# H09R00.net
KiCad netlist of a schematic drawn in EAGLE
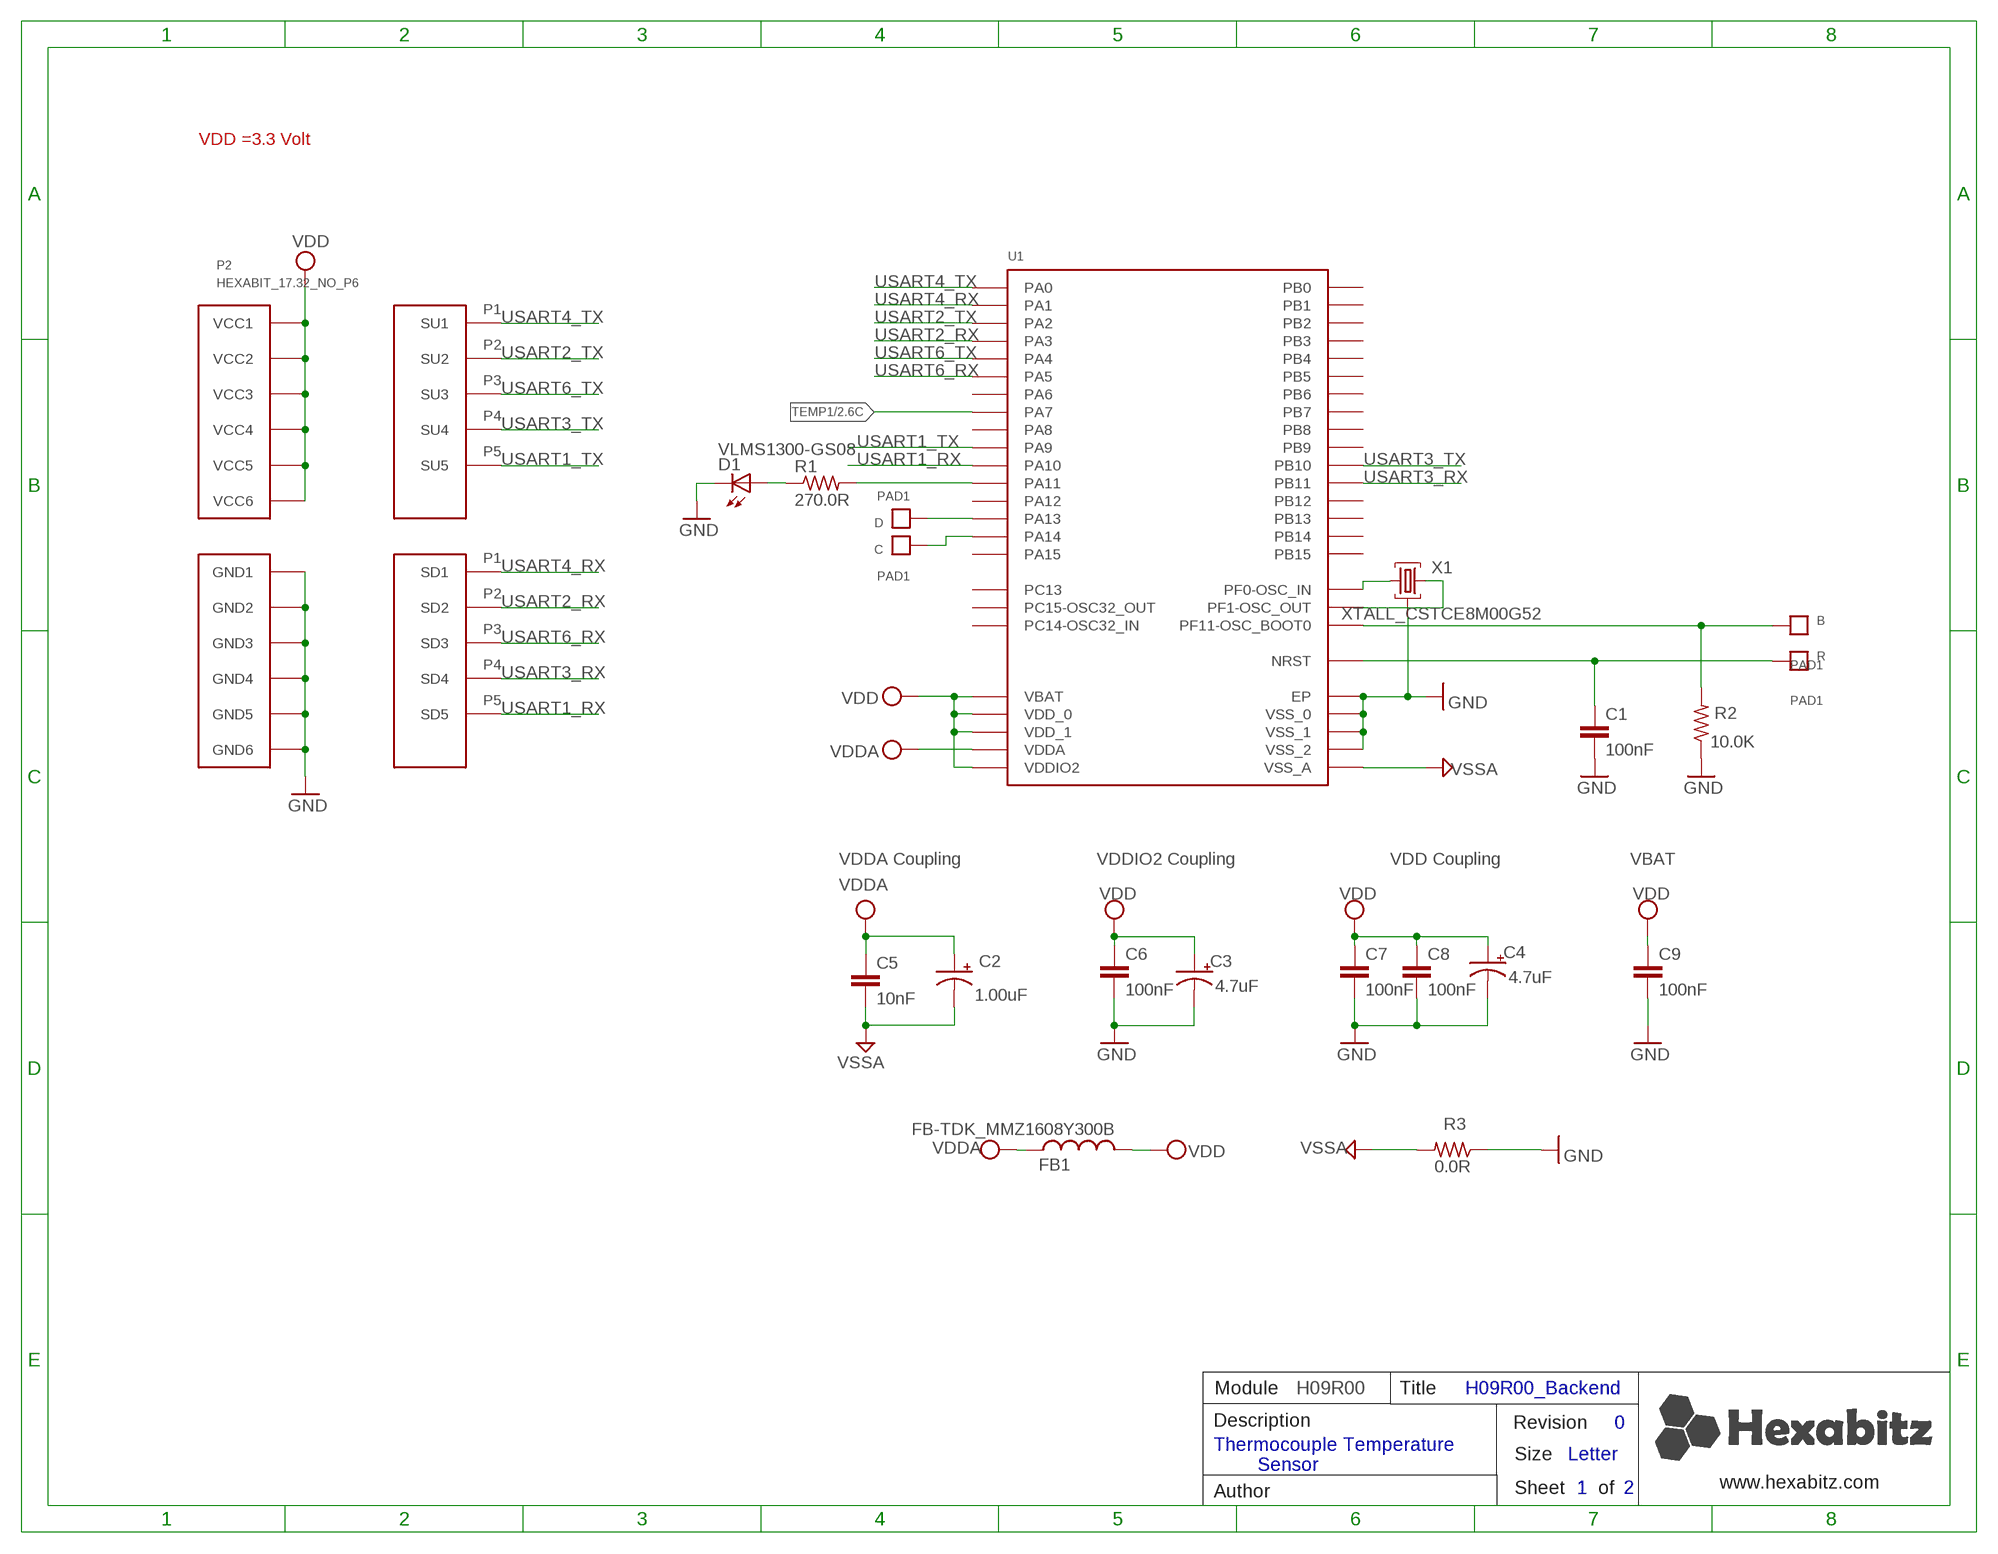
[diagram p0: schematic, sheet 1]
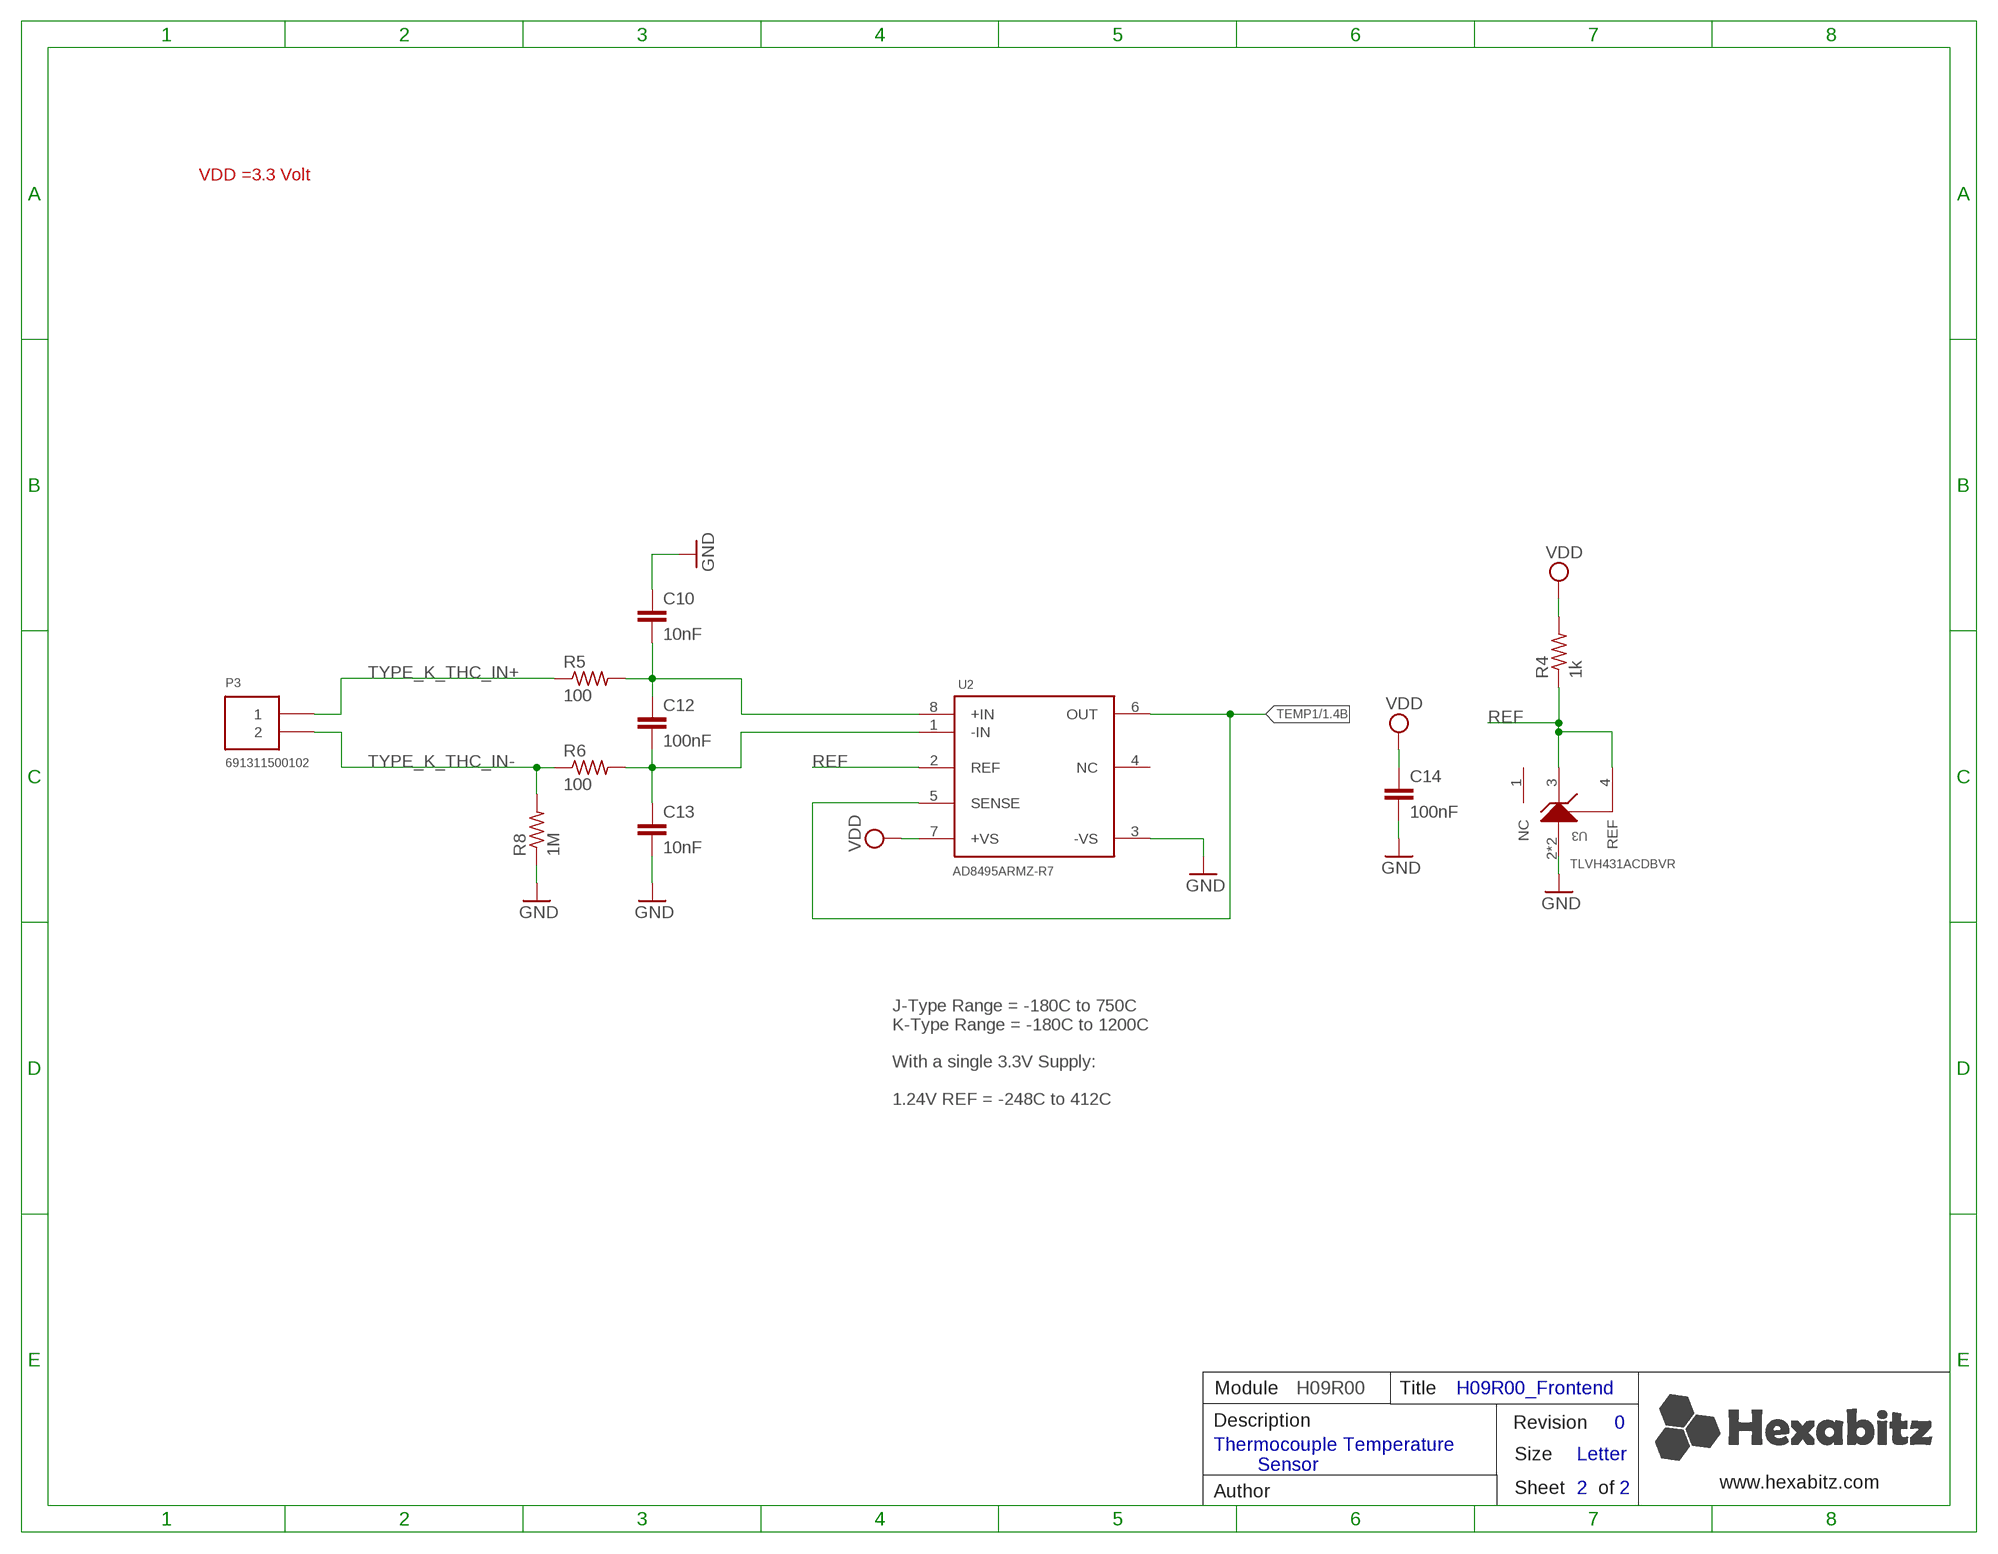
[diagram p1: schematic, sheet 2]

(export (version "E")
  (design (tool "Eeschema 10.0.6"))
  (components
    (comp (ref "B")
      (value "PAD1")
      (footprint "eagle-import:PAD1")
      (libsource (lib "eagle-import") (part "PAD1"))
    )
    (comp (ref "C")
      (value "PAD1")
      (footprint "eagle-import:PAD1")
      (libsource (lib "eagle-import") (part "PAD1"))
    )
    (comp (ref "C1")
      (value "100nF")
      (footprint "eagle-import:C-0603")
      (fields
        (field (name "CAPACITANCE") "100nF")
        (field (name "MFN") "KEMET")
        (field (name "MPN") "C0603C104K8RACTU")
        (field (name "OCTOPART_URL") "https://octopart.com/c0603c104k8ractu-kemet-145075?r=sp&s=9bS9ASSwSEqMCE9KBEQZ0g")
        (field (name "TOLERANCE") "10%")
        (field (name "VOLTAGE_RATING") "10V")
      )
      (libsource (lib "eagle-import") (part "C-0603"))
    )
    (comp (ref "C2")
      (value "1.00uF")
      (footprint "eagle-import:C-0805-POL")
      (fields
        (field (name "CAPACITANCE") "1.00uF")
        (field (name "MFN") "Yageo")
        (field (name "MPN") "CC0805KKX7R7BB105")
        (field (name "OCTOPART_URL") "https://octopart.com/cc0805kkx7r7bb105-yageo-8376555?r=sp&s=YKl1wwtkROau_X5nniH2ig")
        (field (name "TOLERANCE") "10%")
        (field (name "VOLTAGE_RATING") "16V")
      )
      (libsource (lib "eagle-import") (part "C-0805-POL"))
    )
    (comp (ref "C3")
      (value "4.7uF")
      (footprint "eagle-import:C-0805-POL")
      (fields
        (field (name "CAPACITANCE") "4.7uF")
        (field (name "MFN") "Murata")
        (field (name "MPN") "GRM21BC81E475KA12L")
        (field (name "OCTOPART_URL") "https://octopart.com/grm21bc81e475ka12l-murata-10331911?r=sp&s=RY3qZSD8T6mG6TC9CHI5qQ")
        (field (name "TOLERANCE") "10%")
        (field (name "VOLTAGE_RATING") "25V")
      )
      (libsource (lib "eagle-import") (part "C-0805-POL"))
    )
    (comp (ref "C4")
      (value "4.7uF")
      (footprint "eagle-import:C-0805-POL")
      (fields
        (field (name "CAPACITANCE") "4.7uF")
        (field (name "MFN") "Murata")
        (field (name "MPN") "GRM21BC81E475KA12L")
        (field (name "OCTOPART_URL") "https://octopart.com/grm21bc81e475ka12l-murata-10331911?r=sp&s=RY3qZSD8T6mG6TC9CHI5qQ")
        (field (name "TOLERANCE") "10%")
        (field (name "VOLTAGE_RATING") "25V")
      )
      (libsource (lib "eagle-import") (part "C-0805-POL"))
    )
    (comp (ref "C5")
      (value "10nF")
      (footprint "eagle-import:C-0603")
      (fields
        (field (name "CAPACITANCE") "10nF")
        (field (name "MFN") "KEMET")
        (field (name "MPN") "C0603C103K5RACTU")
        (field (name "OCTOPART_URL") "https://octopart.com/c0603c103k5ractu-kemet-133094?r=sp&s=R_iPBxLnSmGqhkU2rIMFpg")
        (field (name "TOLERANCE") "10%")
        (field (name "VOLTAGE_RATING") "50V")
      )
      (libsource (lib "eagle-import") (part "C-0603"))
    )
    (comp (ref "C6")
      (value "100nF")
      (footprint "eagle-import:C-0603")
      (fields
        (field (name "CAPACITANCE") "100nF")
        (field (name "MFN") "KEMET")
        (field (name "MPN") "C0603C104K8RACTU")
        (field (name "OCTOPART_URL") "https://octopart.com/c0603c104k8ractu-kemet-145075?r=sp&s=9bS9ASSwSEqMCE9KBEQZ0g")
        (field (name "TOLERANCE") "10%")
        (field (name "VOLTAGE_RATING") "10V")
      )
      (libsource (lib "eagle-import") (part "C-0603"))
    )
    (comp (ref "C7")
      (value "100nF")
      (footprint "eagle-import:C-0603")
      (fields
        (field (name "CAPACITANCE") "100nF")
        (field (name "MFN") "KEMET")
        (field (name "MPN") "C0603C104K8RACTU")
        (field (name "OCTOPART_URL") "https://octopart.com/c0603c104k8ractu-kemet-145075?r=sp&s=9bS9ASSwSEqMCE9KBEQZ0g")
        (field (name "TOLERANCE") "10%")
        (field (name "VOLTAGE_RATING") "10")
      )
      (libsource (lib "eagle-import") (part "C-0603"))
    )
    (comp (ref "C8")
      (value "100nF")
      (footprint "eagle-import:C-0603")
      (fields
        (field (name "CAPACITANCE") "100nF")
        (field (name "MFN") "KEMET")
        (field (name "MPN") "C0603C104K8RACTU")
        (field (name "OCTOPART_URL") "https://octopart.com/c0603c104k8ractu-kemet-145075?r=sp&s=9bS9ASSwSEqMCE9KBEQZ0g")
        (field (name "TOLERANCE") "10%")
        (field (name "VOLTAGE_RATING") "10V")
      )
      (libsource (lib "eagle-import") (part "C-0603"))
    )
    (comp (ref "C9")
      (value "100nF")
      (footprint "eagle-import:C-0603")
      (fields
        (field (name "CAPACITANCE") "100nF")
        (field (name "MFN") "KEMET")
        (field (name "MPN") "C0603C104K8RACTU")
        (field (name "OCTOPART_URL") "https://octopart.com/c0603c104k8ractu-kemet-145075?r=sp&s=9bS9ASSwSEqMCE9KBEQZ0g")
        (field (name "TOLERANCE") "10V")
        (field (name "VOLTAGE_RATING") "10%")
      )
      (libsource (lib "eagle-import") (part "C-0603"))
    )
    (comp (ref "D")
      (value "PAD1")
      (footprint "eagle-import:PAD1")
      (libsource (lib "eagle-import") (part "PAD1"))
    )
    (comp (ref "D1")
      (value "VLMS1300-GS08")
      (footprint "eagle-import:VLMS1300-GS08")
      (fields
        (field (name "MFN") "Vishay")
        (field (name "MPN") "VLMS1300-GS08")
        (field (name "OCTOPART_URL") "https://octopart.com/vlms1300-gs08-vishay-21709201?r=sp&s=_gcP4_q8T1SC6PJQPTQ9yA")
      )
      (libsource (lib "eagle-import") (part "VLMS1300-GS08"))
    )
    (comp (ref "FB1")
      (value "FB-TDK_MMZ1608Y300B")
      (footprint "eagle-import:FB-TDK_MMZ1608Y300B")
      (fields
        (field (name "MFN") "TDK ")
        (field (name "MPN") "MMZ1608Y300B")
        (field (name "OCTOPART_URL") "https://octopart.com/mmz1608y300b-tdk-368280?r=sp&s=cd9_2ZEqQ9q9UNBuQgHAiA")
      )
      (libsource (lib "eagle-import") (part "FB-TDK_MMZ1608Y300B"))
    )
    (comp (ref "P2")
      (value "HEXABIT_17.32_NO_P6")
      (footprint "eagle-import:HEXABIT_17.32_NO_P6")
      (libsource (lib "eagle-import") (part "HEXABIT_17.32_NO_P6"))
    )
    (comp (ref "R")
      (value "PAD1")
      (footprint "eagle-import:PAD1")
      (libsource (lib "eagle-import") (part "PAD1"))
    )
    (comp (ref "R1")
      (value "270.0R")
      (footprint "eagle-import:R-0603")
      (fields
        (field (name "MFN") "Yageo")
        (field (name "MPN") "RC0603FR-07270RL")
        (field (name "OCTOPART_URL") "https://octopart.com/search?q=RC0603FR-07270RL&start=0")
        (field (name "RESISTANCE") "270.0 Ohm")
        (field (name "TOLERANCE") "1%")
      )
      (libsource (lib "eagle-import") (part "R-0603"))
    )
    (comp (ref "R2")
      (value "10.0K")
      (footprint "eagle-import:R-0603")
      (fields
        (field (name "MFN") "Yageo")
        (field (name "MPN") "RC0603JR-0710KL")
        (field (name "OCTOPART_URL") "https://octopart.com/search?q=RC0603JR-0710KL&start=0")
        (field (name "RESISTANCE") "10.0K Ohm")
        (field (name "TOLERANCE") "5%")
      )
      (libsource (lib "eagle-import") (part "R-0603"))
    )
    (comp (ref "R3")
      (value "0.0R")
      (footprint "eagle-import:R-0603")
      (fields
        (field (name "MFN") "Yageo")
        (field (name "MPN") "RC0603JR-070RL")
        (field (name "OCTOPART_URL") "https://octopart.com/rc0603jr-070rl-yageo-1241539?r=sp&s=X2NteqRjRNWrnx42Y0aliA")
        (field (name "RESISTANCE") "0.0 Ohm")
      )
      (libsource (lib "eagle-import") (part "R-0603"))
    )
    (comp (ref "U1")
      (value "STM32F091CBU6")
      (footprint "eagle-import:STM32F091CBU6")
      (libsource (lib "eagle-import") (part "STM32F091CBU6"))
    )
    (comp (ref "X1")
      (value "XTALL_CSTCE8M00G52")
      (footprint "eagle-import:XTALL_CSTCE8M00G52")
      (fields (field (name "MPN") "CSTCE8M00G52Z-R0"))
      (libsource (lib "eagle-import") (part "XTALL_CSTCE8M00G52"))
    )
    (comp (ref "C10")
      (value "10nF")
      (footprint "eagle-import:C-0603")
      (fields
        (field (name "CAPACITANCE") "10nF")
        (field (name "MFN") "KEMET")
        (field (name "MPN") "C0603C103K5RACTU")
        (field (name "OCTOPART_URL") "https://octopart.com/c0603c103k5ractu-kemet-133094?r=sp&s=R_iPBxLnSmGqhkU2rIMFpg")
        (field (name "TOLERANCE") "10%")
        (field (name "VOLTAGE_RATING") "50V")
      )
      (libsource (lib "eagle-import") (part "C-0603"))
    )
    (comp (ref "C12")
      (value "100nF")
      (footprint "eagle-import:C-0603")
      (fields
        (field (name "CAPACITANCE") "100nF")
        (field (name "MFN") "KEMET")
        (field (name "MPN") "C0603C104K8RACTU")
        (field (name "OCTOPART_URL") "https://octopart.com/c0603c104k8ractu-kemet-145075?r=sp&s=9bS9ASSwSEqMCE9KBEQZ0g")
        (field (name "TOLERANCE") "10%")
        (field (name "VOLTAGE_RATING") "10V")
      )
      (libsource (lib "eagle-import") (part "C-0603"))
    )
    (comp (ref "C13")
      (value "10nF")
      (footprint "eagle-import:C-0603")
      (fields
        (field (name "CAPACITANCE") "10nF")
        (field (name "MFN") "KEMET")
        (field (name "MPN") "C0603C103K5RACTU")
        (field (name "OCTOPART_URL") "https://octopart.com/c0603c103k5ractu-kemet-133094?r=sp&s=R_iPBxLnSmGqhkU2rIMFpg")
        (field (name "TOLERANCE") "10%")
        (field (name "VOLTAGE_RATING") "50V")
      )
      (libsource (lib "eagle-import") (part "C-0603"))
    )
    (comp (ref "C14")
      (value "100nF")
      (footprint "eagle-import:C-0603")
      (fields
        (field (name "CAPACITANCE") "100nF")
        (field (name "MFN") "KEMET")
        (field (name "MPN") "C0603C104K8RACTU")
        (field (name "OCTOPART_URL") "https://octopart.com/c0603c104k8ractu-kemet-145075?r=sp&s=9bS9ASSwSEqMCE9KBEQZ0g")
        (field (name "TOLERANCE") "10%")
        (field (name "VOLTAGE_RATING") "10V")
      )
      (libsource (lib "eagle-import") (part "C-0603"))
    )
    (comp (ref "P3")
      (value "691311500102")
      (footprint "eagle-import:691311500102")
      (fields (field (name "MPN") "Wurth Electronics Inc."))
      (libsource (lib "eagle-import") (part "691311500102"))
    )
    (comp (ref "R4")
      (value "1k")
      (footprint "eagle-import:R-0402")
      (fields
        (field (name "MFN") "Yageo")
        (field (name "MPN") "RC0402FR-071KL")
        (field (name "OCTOPART_URL") "https://octopart.com/search?q=RC0402FR-071KL&start=0")
        (field (name "RESISTANCE") "1k")
        (field (name "TOLERANCE") "1%")
      )
      (libsource (lib "eagle-import") (part "R-0402"))
    )
    (comp (ref "R5")
      (value "100")
      (footprint "eagle-import:R-0402")
      (fields
        (field (name "MFN") "Yageo")
        (field (name "MPN") "RC0402FR-07100RL")
        (field (name "OCTOPART_URL") "https://octopart.com/search?q=RC0402FR-07100RL&start=0")
        (field (name "RESISTANCE") "100")
        (field (name "TOLERANCE") "1%")
      )
      (libsource (lib "eagle-import") (part "R-0402"))
    )
    (comp (ref "R6")
      (value "100")
      (footprint "eagle-import:R-0402")
      (fields
        (field (name "MFN") "Yageo")
        (field (name "MPN") "RC0402FR-07100RL")
        (field (name "OCTOPART_URL") "https://octopart.com/search?q=RC0402FR-07100RL&start=0")
        (field (name "RESISTANCE") "100")
        (field (name "TOLERANCE") "1%")
      )
      (libsource (lib "eagle-import") (part "R-0402"))
    )
    (comp (ref "R8")
      (value "1M")
      (footprint "eagle-import:R-0402")
      (fields
        (field (name "MFN") "Yageo")
        (field (name "MPN") "RC0402FR-071ML")
        (field (name "OCTOPART_URL") "https://octopart.com/search?q=RC0402FR-071ML&start=0")
        (field (name "RESISTANCE") "1M")
        (field (name "TOLERANCE") "1%")
      )
      (libsource (lib "eagle-import") (part "R-0402"))
    )
    (comp (ref "U2")
      (value "AD8495ARMZ-R7")
      (footprint "eagle-import:AD8495ARMZ")
      (fields (field (name "MFG") "Analog Devices"))
      (libsource (lib "eagle-import") (part "AD8495ARMZ"))
    )
    (comp (ref "U3")
      (value "TLVH431ACDBVR")
      (footprint "eagle-import:TLVH431ACDBVR")
      (libsource (lib "eagle-import") (part "TLVH431ACDBVR"))
    )
  )
  (nets
    (net (code "1") (name "GND") (class "Default")
      (node (ref "C1") (pin "2") (pinfunction "2_2") (pintype "passive"))
      (node (ref "C10") (pin "1") (pinfunction "1_1") (pintype "passive"))
      (node (ref "C13") (pin "2") (pinfunction "2_2") (pintype "passive"))
      (node (ref "C14") (pin "2") (pinfunction "2_2") (pintype "passive"))
      (node (ref "C3") (pin "2") (pinfunction "-_2") (pintype "passive"))
      (node (ref "C4") (pin "2") (pinfunction "-_2") (pintype "passive"))
      (node (ref "C6") (pin "2") (pinfunction "2_2") (pintype "passive"))
      (node (ref "C7") (pin "2") (pinfunction "2_2") (pintype "passive"))
      (node (ref "C8") (pin "2") (pinfunction "2_2") (pintype "passive"))
      (node (ref "C9") (pin "2") (pinfunction "2_2") (pintype "passive"))
      (node (ref "D1") (pin "C") (pinfunction "C_C") (pintype "passive"))
      (node (ref "P2") (pin "10") (pinfunction "GND4_10") (pintype "power_in"))
      (node (ref "P2") (pin "11") (pinfunction "GND5_11") (pintype "power_in"))
      (node (ref "P2") (pin "12") (pinfunction "GND6_12") (pintype "power_in"))
      (node (ref "P2") (pin "7") (pinfunction "GND1_7") (pintype "power_in"))
      (node (ref "P2") (pin "8") (pinfunction "GND2_8") (pintype "power_in"))
      (node (ref "P2") (pin "9") (pinfunction "GND3_9") (pintype "power_in"))
      (node (ref "R2") (pin "1") (pinfunction "1_1") (pintype "passive"))
      (node (ref "R3") (pin "1") (pinfunction "1_1") (pintype "passive"))
      (node (ref "R8") (pin "1") (pinfunction "1_1") (pintype "passive"))
      (node (ref "U1") (pin "EP") (pinfunction "EP_EP") (pintype "power_in"))
      (node (ref "U1") (pin "P$23") (pinfunction "VSS_0_P$23") (pintype "power_in"))
      (node (ref "U1") (pin "P$35") (pinfunction "VSS_1_P$35") (pintype "power_in"))
      (node (ref "U1") (pin "P$47") (pinfunction "VSS_2_P$47") (pintype "power_in"))
      (node (ref "U2") (pin "3") (pinfunction "-VS_3") (pintype "power_in"))
      (node (ref "U3") (pin "2") (pinfunction "ANODE_2") (pintype "input"))
      (node (ref "U3") (pin "5") (pinfunction "ANODE_5") (pintype "input"))
      (node (ref "X1") (pin "P$2") (pinfunction "2_P$2") (pintype "passive"))
    )
    (net (code "2") (name "Net-(D1-PadA)") (class "Default")
      (node (ref "D1") (pin "A") (pinfunction "A_A") (pintype "passive"))
      (node (ref "R1") (pin "1") (pinfunction "1_1") (pintype "passive"))
    )
    (net (code "3") (name "Net-(U1-NRST)") (class "Default")
      (node (ref "C1") (pin "1") (pinfunction "1_1") (pintype "passive"))
      (node (ref "R") (pin "P$1") (pinfunction "P$1_P$1") (pintype "passive"))
      (node (ref "R") (pin "P$2") (pinfunction "P$1_P$2") (pintype "passive"))
      (node (ref "U1") (pin "P$7") (pinfunction "NRST_P$7") (pintype "passive"))
    )
    (net (code "4") (name "Net-(U1-PA11)") (class "Default")
      (node (ref "R1") (pin "2") (pinfunction "2_2") (pintype "passive"))
      (node (ref "U1") (pin "P$32") (pinfunction "PA11_P$32") (pintype "bidirectional"))
    )
    (net (code "5") (name "Net-(U1-PA13)") (class "Default")
      (node (ref "D") (pin "P$1") (pinfunction "P$1_P$1") (pintype "passive"))
      (node (ref "D") (pin "P$2") (pinfunction "P$1_P$2") (pintype "passive"))
      (node (ref "U1") (pin "P$34") (pinfunction "PA13_P$34") (pintype "bidirectional"))
    )
    (net (code "6") (name "Net-(U1-PA14)") (class "Default")
      (node (ref "C") (pin "P$1") (pinfunction "P$1_P$1") (pintype "passive"))
      (node (ref "C") (pin "P$2") (pinfunction "P$1_P$2") (pintype "passive"))
      (node (ref "U1") (pin "P$37") (pinfunction "PA14_P$37") (pintype "bidirectional"))
    )
    (net (code "7") (name "Net-(U1-PF0-OSC_IN)") (class "Default")
      (node (ref "U1") (pin "P$5") (pinfunction "PF0-OSC_IN_P$5") (pintype "bidirectional"))
      (node (ref "X1") (pin "P$1") (pinfunction "1_P$1") (pintype "passive"))
    )
    (net (code "8") (name "Net-(U1-PF1-OSC_OUT)") (class "Default")
      (node (ref "U1") (pin "P$6") (pinfunction "PF1-OSC_OUT_P$6") (pintype "bidirectional"))
      (node (ref "X1") (pin "P$3") (pinfunction "3_P$3") (pintype "passive"))
    )
    (net (code "9") (name "Net-(U1-PF11-OSC_BOOT0)") (class "Default")
      (node (ref "B") (pin "P$1") (pinfunction "P$1_P$1") (pintype "passive"))
      (node (ref "B") (pin "P$2") (pinfunction "P$1_P$2") (pintype "passive"))
      (node (ref "R2") (pin "2") (pinfunction "2_2") (pintype "passive"))
      (node (ref "U1") (pin "P$44") (pinfunction "PF11-OSC_BOOT0_P$44") (pintype "bidirectional"))
    )
    (net (code "10") (name "Net-(U2-+IN)") (class "Default")
      (node (ref "C10") (pin "2") (pinfunction "2_2") (pintype "passive"))
      (node (ref "C12") (pin "1") (pinfunction "1_1") (pintype "passive"))
      (node (ref "R5") (pin "2") (pinfunction "2_2") (pintype "passive"))
      (node (ref "U2") (pin "8") (pinfunction "+IN_8") (pintype "bidirectional"))
    )
    (net (code "11") (name "Net-(U2--IN)") (class "Default")
      (node (ref "C12") (pin "2") (pinfunction "2_2") (pintype "passive"))
      (node (ref "C13") (pin "1") (pinfunction "1_1") (pintype "passive"))
      (node (ref "R6") (pin "2") (pinfunction "2_2") (pintype "passive"))
      (node (ref "U2") (pin "1") (pinfunction "-IN_1") (pintype "bidirectional"))
    )
    (net (code "12") (name "REF") (class "Default")
      (node (ref "R4") (pin "1") (pinfunction "1_1") (pintype "passive"))
      (node (ref "U2") (pin "2") (pinfunction "REF_2") (pintype "bidirectional"))
      (node (ref "U3") (pin "3") (pinfunction "CATHODE_3") (pintype "output"))
      (node (ref "U3") (pin "4") (pinfunction "REF_4") (pintype "input"))
    )
    (net (code "13") (name "TEMP1") (class "Default")
      (node (ref "U1") (pin "P$17") (pinfunction "PA7_P$17") (pintype "bidirectional"))
      (node (ref "U2") (pin "5") (pinfunction "SENSE_5") (pintype "bidirectional"))
      (node (ref "U2") (pin "6") (pinfunction "OUT_6") (pintype "output"))
    )
    (net (code "14") (name "TYPE_K_THC_IN+") (class "Default")
      (node (ref "P3") (pin "1") (pinfunction "1_1") (pintype "power_in"))
      (node (ref "R5") (pin "1") (pinfunction "1_1") (pintype "passive"))
    )
    (net (code "15") (name "TYPE_K_THC_IN-") (class "Default")
      (node (ref "P3") (pin "2") (pinfunction "2_2") (pintype "power_in"))
      (node (ref "R6") (pin "1") (pinfunction "1_1") (pintype "passive"))
      (node (ref "R8") (pin "2") (pinfunction "2_2") (pintype "passive"))
    )
    (net (code "16") (name "USART1_RX") (class "Default")
      (node (ref "P2") (pin "23") (pinfunction "SD5_23") (pintype "bidirectional"))
      (node (ref "U1") (pin "P$31") (pinfunction "PA10_P$31") (pintype "bidirectional"))
    )
    (net (code "17") (name "USART1_TX") (class "Default")
      (node (ref "P2") (pin "17") (pinfunction "SU5_17") (pintype "bidirectional"))
      (node (ref "U1") (pin "P$30") (pinfunction "PA9_P$30") (pintype "bidirectional"))
    )
    (net (code "18") (name "USART2_RX") (class "Default")
      (node (ref "P2") (pin "20") (pinfunction "SD2_20") (pintype "bidirectional"))
      (node (ref "U1") (pin "P$13") (pinfunction "PA3_P$13") (pintype "bidirectional"))
    )
    (net (code "19") (name "USART2_TX") (class "Default")
      (node (ref "P2") (pin "14") (pinfunction "SU2_14") (pintype "bidirectional"))
      (node (ref "U1") (pin "P$12") (pinfunction "PA2_P$12") (pintype "bidirectional"))
    )
    (net (code "20") (name "USART3_RX") (class "Default")
      (node (ref "P2") (pin "22") (pinfunction "SD4_22") (pintype "bidirectional"))
      (node (ref "U1") (pin "P$22") (pinfunction "PB11_P$22") (pintype "bidirectional"))
    )
    (net (code "21") (name "USART3_TX") (class "Default")
      (node (ref "P2") (pin "16") (pinfunction "SU4_16") (pintype "bidirectional"))
      (node (ref "U1") (pin "P$21") (pinfunction "PB10_P$21") (pintype "bidirectional"))
    )
    (net (code "22") (name "USART4_RX") (class "Default")
      (node (ref "P2") (pin "19") (pinfunction "SD1_19") (pintype "bidirectional"))
      (node (ref "U1") (pin "P$11") (pinfunction "PA1_P$11") (pintype "bidirectional"))
    )
    (net (code "23") (name "USART4_TX") (class "Default")
      (node (ref "P2") (pin "13") (pinfunction "SU1_13") (pintype "bidirectional"))
      (node (ref "U1") (pin "P$10") (pinfunction "PA0_P$10") (pintype "bidirectional"))
    )
    (net (code "24") (name "USART6_RX") (class "Default")
      (node (ref "P2") (pin "21") (pinfunction "SD3_21") (pintype "bidirectional"))
      (node (ref "U1") (pin "P$15") (pinfunction "PA5_P$15") (pintype "bidirectional"))
    )
    (net (code "25") (name "USART6_TX") (class "Default")
      (node (ref "P2") (pin "15") (pinfunction "SU3_15") (pintype "bidirectional"))
      (node (ref "U1") (pin "P$14") (pinfunction "PA4_P$14") (pintype "bidirectional"))
    )
    (net (code "26") (name "VDD") (class "Default")
      (node (ref "C14") (pin "1") (pinfunction "1_1") (pintype "passive"))
      (node (ref "C3") (pin "1") (pinfunction "+_1") (pintype "passive"))
      (node (ref "C4") (pin "1") (pinfunction "+_1") (pintype "passive"))
      (node (ref "C6") (pin "1") (pinfunction "1_1") (pintype "passive"))
      (node (ref "C7") (pin "1") (pinfunction "1_1") (pintype "passive"))
      (node (ref "C8") (pin "1") (pinfunction "1_1") (pintype "passive"))
      (node (ref "C9") (pin "1") (pinfunction "1_1") (pintype "passive"))
      (node (ref "FB1") (pin "2") (pinfunction "2_2") (pintype "passive"))
      (node (ref "P2") (pin "1") (pinfunction "VCC1_1") (pintype "power_in"))
      (node (ref "P2") (pin "2") (pinfunction "VCC2_2") (pintype "power_in"))
      (node (ref "P2") (pin "3") (pinfunction "VCC3_3") (pintype "power_in"))
      (node (ref "P2") (pin "4") (pinfunction "VCC4_4") (pintype "power_in"))
      (node (ref "P2") (pin "5") (pinfunction "VCC5_5") (pintype "power_in"))
      (node (ref "P2") (pin "6") (pinfunction "VCC6_6") (pintype "power_in"))
      (node (ref "R4") (pin "2") (pinfunction "2_2") (pintype "passive"))
      (node (ref "U1") (pin "P$1") (pinfunction "VBAT_P$1") (pintype "power_in"))
      (node (ref "U1") (pin "P$24") (pinfunction "VDD_0_P$24") (pintype "power_in"))
      (node (ref "U1") (pin "P$36") (pinfunction "VDDIO2_P$36") (pintype "power_in"))
      (node (ref "U1") (pin "P$48") (pinfunction "VDD_1_P$48") (pintype "power_in"))
      (node (ref "U2") (pin "7") (pinfunction "+VS_7") (pintype "power_in"))
    )
    (net (code "27") (name "VDDA") (class "Default")
      (node (ref "C2") (pin "1") (pinfunction "+_1") (pintype "passive"))
      (node (ref "C5") (pin "1") (pinfunction "1_1") (pintype "passive"))
      (node (ref "FB1") (pin "1") (pinfunction "1_1") (pintype "passive"))
      (node (ref "U1") (pin "P$9") (pinfunction "VDDA_P$9") (pintype "power_in"))
    )
    (net (code "28") (name "VSSA") (class "Default")
      (node (ref "C2") (pin "2") (pinfunction "-_2") (pintype "passive"))
      (node (ref "C5") (pin "2") (pinfunction "2_2") (pintype "passive"))
      (node (ref "R3") (pin "2") (pinfunction "2_2") (pintype "passive"))
      (node (ref "U1") (pin "P$8") (pinfunction "VSS_A_P$8") (pintype "power_in"))
    )
    (net (code "29") (name "unconnected-(U1-PA6-PadP$16)") (class "Default")
      (node (ref "U1") (pin "P$16") (pinfunction "PA6_P$16") (pintype "bidirectional"))
    )
    (net (code "30") (name "unconnected-(U1-PA8-PadP$29)") (class "Default")
      (node (ref "U1") (pin "P$29") (pinfunction "PA8_P$29") (pintype "bidirectional"))
    )
    (net (code "31") (name "unconnected-(U1-PA12-PadP$33)") (class "Default")
      (node (ref "U1") (pin "P$33") (pinfunction "PA12_P$33") (pintype "bidirectional"))
    )
    (net (code "32") (name "unconnected-(U1-PA15-PadP$38)") (class "Default")
      (node (ref "U1") (pin "P$38") (pinfunction "PA15_P$38") (pintype "bidirectional"))
    )
    (net (code "33") (name "unconnected-(U1-PB0-PadP$18)") (class "Default")
      (node (ref "U1") (pin "P$18") (pinfunction "PB0_P$18") (pintype "bidirectional"))
    )
    (net (code "34") (name "unconnected-(U1-PB1-PadP$19)") (class "Default")
      (node (ref "U1") (pin "P$19") (pinfunction "PB1_P$19") (pintype "bidirectional"))
    )
    (net (code "35") (name "unconnected-(U1-PB2-PadP$20)") (class "Default")
      (node (ref "U1") (pin "P$20") (pinfunction "PB2_P$20") (pintype "bidirectional"))
    )
    (net (code "36") (name "unconnected-(U1-PB3-PadP$39)") (class "Default")
      (node (ref "U1") (pin "P$39") (pinfunction "PB3_P$39") (pintype "bidirectional"))
    )
    (net (code "37") (name "unconnected-(U1-PB4-PadP$40)") (class "Default")
      (node (ref "U1") (pin "P$40") (pinfunction "PB4_P$40") (pintype "bidirectional"))
    )
    (net (code "38") (name "unconnected-(U1-PB5-PadP$41)") (class "Default")
      (node (ref "U1") (pin "P$41") (pinfunction "PB5_P$41") (pintype "bidirectional"))
    )
    (net (code "39") (name "unconnected-(U1-PB6-PadP$42)") (class "Default")
      (node (ref "U1") (pin "P$42") (pinfunction "PB6_P$42") (pintype "bidirectional"))
    )
    (net (code "40") (name "unconnected-(U1-PB7-PadP$43)") (class "Default")
      (node (ref "U1") (pin "P$43") (pinfunction "PB7_P$43") (pintype "bidirectional"))
    )
    (net (code "41") (name "unconnected-(U1-PB8-PadP$45)") (class "Default")
      (node (ref "U1") (pin "P$45") (pinfunction "PB8_P$45") (pintype "bidirectional"))
    )
    (net (code "42") (name "unconnected-(U1-PB9-PadP$46)") (class "Default")
      (node (ref "U1") (pin "P$46") (pinfunction "PB9_P$46") (pintype "bidirectional"))
    )
    (net (code "43") (name "unconnected-(U1-PB12-PadP$25)") (class "Default")
      (node (ref "U1") (pin "P$25") (pinfunction "PB12_P$25") (pintype "bidirectional"))
    )
    (net (code "44") (name "unconnected-(U1-PB13-PadP$26)") (class "Default")
      (node (ref "U1") (pin "P$26") (pinfunction "PB13_P$26") (pintype "bidirectional"))
    )
    (net (code "45") (name "unconnected-(U1-PB14-PadP$27)") (class "Default")
      (node (ref "U1") (pin "P$27") (pinfunction "PB14_P$27") (pintype "bidirectional"))
    )
    (net (code "46") (name "unconnected-(U1-PB15-PadP$28)") (class "Default")
      (node (ref "U1") (pin "P$28") (pinfunction "PB15_P$28") (pintype "bidirectional"))
    )
    (net (code "47") (name "unconnected-(U1-PC13-PadP$2)") (class "Default")
      (node (ref "U1") (pin "P$2") (pinfunction "PC13_P$2") (pintype "bidirectional"))
    )
    (net (code "48") (name "unconnected-(U1-PC14-OSC32_IN-PadP$3)") (class "Default")
      (node (ref "U1") (pin "P$3") (pinfunction "PC14-OSC32_IN_P$3") (pintype "bidirectional"))
    )
    (net (code "49") (name "unconnected-(U1-PC15-OSC32_OUT-PadP$4)") (class "Default")
      (node (ref "U1") (pin "P$4") (pinfunction "PC15-OSC32_OUT_P$4") (pintype "bidirectional"))
    )
    (net (code "50") (name "unconnected-(U2-NC-Pad4)") (class "Default")
      (node (ref "U2") (pin "4") (pinfunction "NC_4") (pintype "no_connect"))
    )
    (net (code "51") (name "unconnected-(U3-NC-Pad1)") (class "Default")
      (node (ref "U3") (pin "1") (pinfunction "NC_1") (pintype "no_connect"))
    )
  )
)
